# BUTTON.net
KiCad netlist of a schematic drawn in Altium Designer
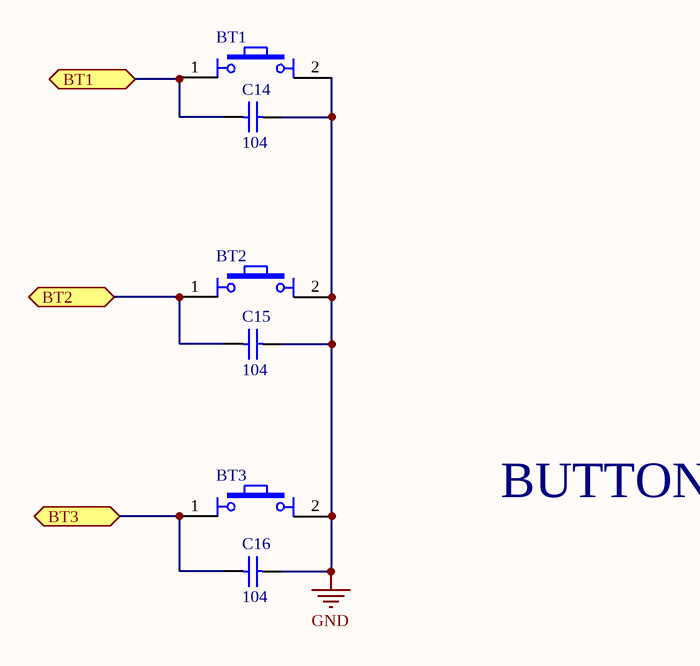
[diagram p0: BUTTON.SchDoc]

(export (version "E")
  (design (tool "Eeschema 10.0.6"))
  (components
    (comp (ref "BT1")
      (value "Nut Nhan 4 Chan Cam 6x6")
      (footprint "Nut Nhan 4 Chan Cam 6x6")
      (description "Nut Nhan 4 Chan 6x6mm")
      (libsource (lib "Altium_Lib_by_KhueNguyenCreator") (part "Nut Nhan 4 Chan Cam 6x6"))
    )
    (comp (ref "BT2")
      (value "Nut Nhan 4 Chan Cam 6x6")
      (footprint "Nut Nhan 4 Chan Cam 6x6")
      (description "Nut Nhan 4 Chan 6x6mm")
      (libsource (lib "Altium_Lib_by_KhueNguyenCreator") (part "Nut Nhan 4 Chan Cam 6x6"))
    )
    (comp (ref "BT3")
      (value "Nut Nhan 4 Chan Cam 6x6")
      (footprint "Nut Nhan 4 Chan Cam 6x6")
      (description "Nut Nhan 4 Chan 6x6mm")
      (libsource (lib "Altium_Lib_by_KhueNguyenCreator") (part "Nut Nhan 4 Chan Cam 6x6"))
    )
    (comp (ref "C14")
      (value "104")
      (footprint "tu 0603")
      (description "Dán")
      (libsource (lib "Altium_Lib_by_KhueNguyenCreator") (part "Tu 0603 104 50V 10%"))
    )
    (comp (ref "C15")
      (value "104")
      (footprint "tu 0603")
      (description "Dán")
      (libsource (lib "Altium_Lib_by_KhueNguyenCreator") (part "Tu 0603 104 50V 10%"))
    )
    (comp (ref "C16")
      (value "104")
      (footprint "tu 0603")
      (description "Dán")
      (libsource (lib "Altium_Lib_by_KhueNguyenCreator") (part "Tu 0603 104 50V 10%"))
    )
  )
  (nets
    (net (code "1") (name "/BT1") (class "Default")
      (node (ref "BT1") (pin "1") (pintype "passive"))
      (node (ref "C14") (pin "2") (pinfunction "2_2") (pintype "passive"))
    )
    (net (code "2") (name "/BT2") (class "Default")
      (node (ref "BT2") (pin "1") (pintype "passive"))
      (node (ref "C15") (pin "2") (pinfunction "2_2") (pintype "passive"))
    )
    (net (code "3") (name "/BT3") (class "Default")
      (node (ref "BT3") (pin "1") (pintype "passive"))
      (node (ref "C16") (pin "2") (pinfunction "2_2") (pintype "passive"))
    )
    (net (code "4") (name "GND") (class "Default")
      (node (ref "BT1") (pin "2") (pintype "passive"))
      (node (ref "BT2") (pin "2") (pintype "passive"))
      (node (ref "BT3") (pin "2") (pintype "passive"))
      (node (ref "C14") (pin "1") (pinfunction "1_1") (pintype "passive"))
      (node (ref "C15") (pin "1") (pinfunction "1_1") (pintype "passive"))
      (node (ref "C16") (pin "1") (pinfunction "1_1") (pintype "passive"))
    )
  )
)
